# ProPrj_hdmi_3in1out_2024-07-09.net
KiCad netlist of a schematic drawn in EasyEDA Pro
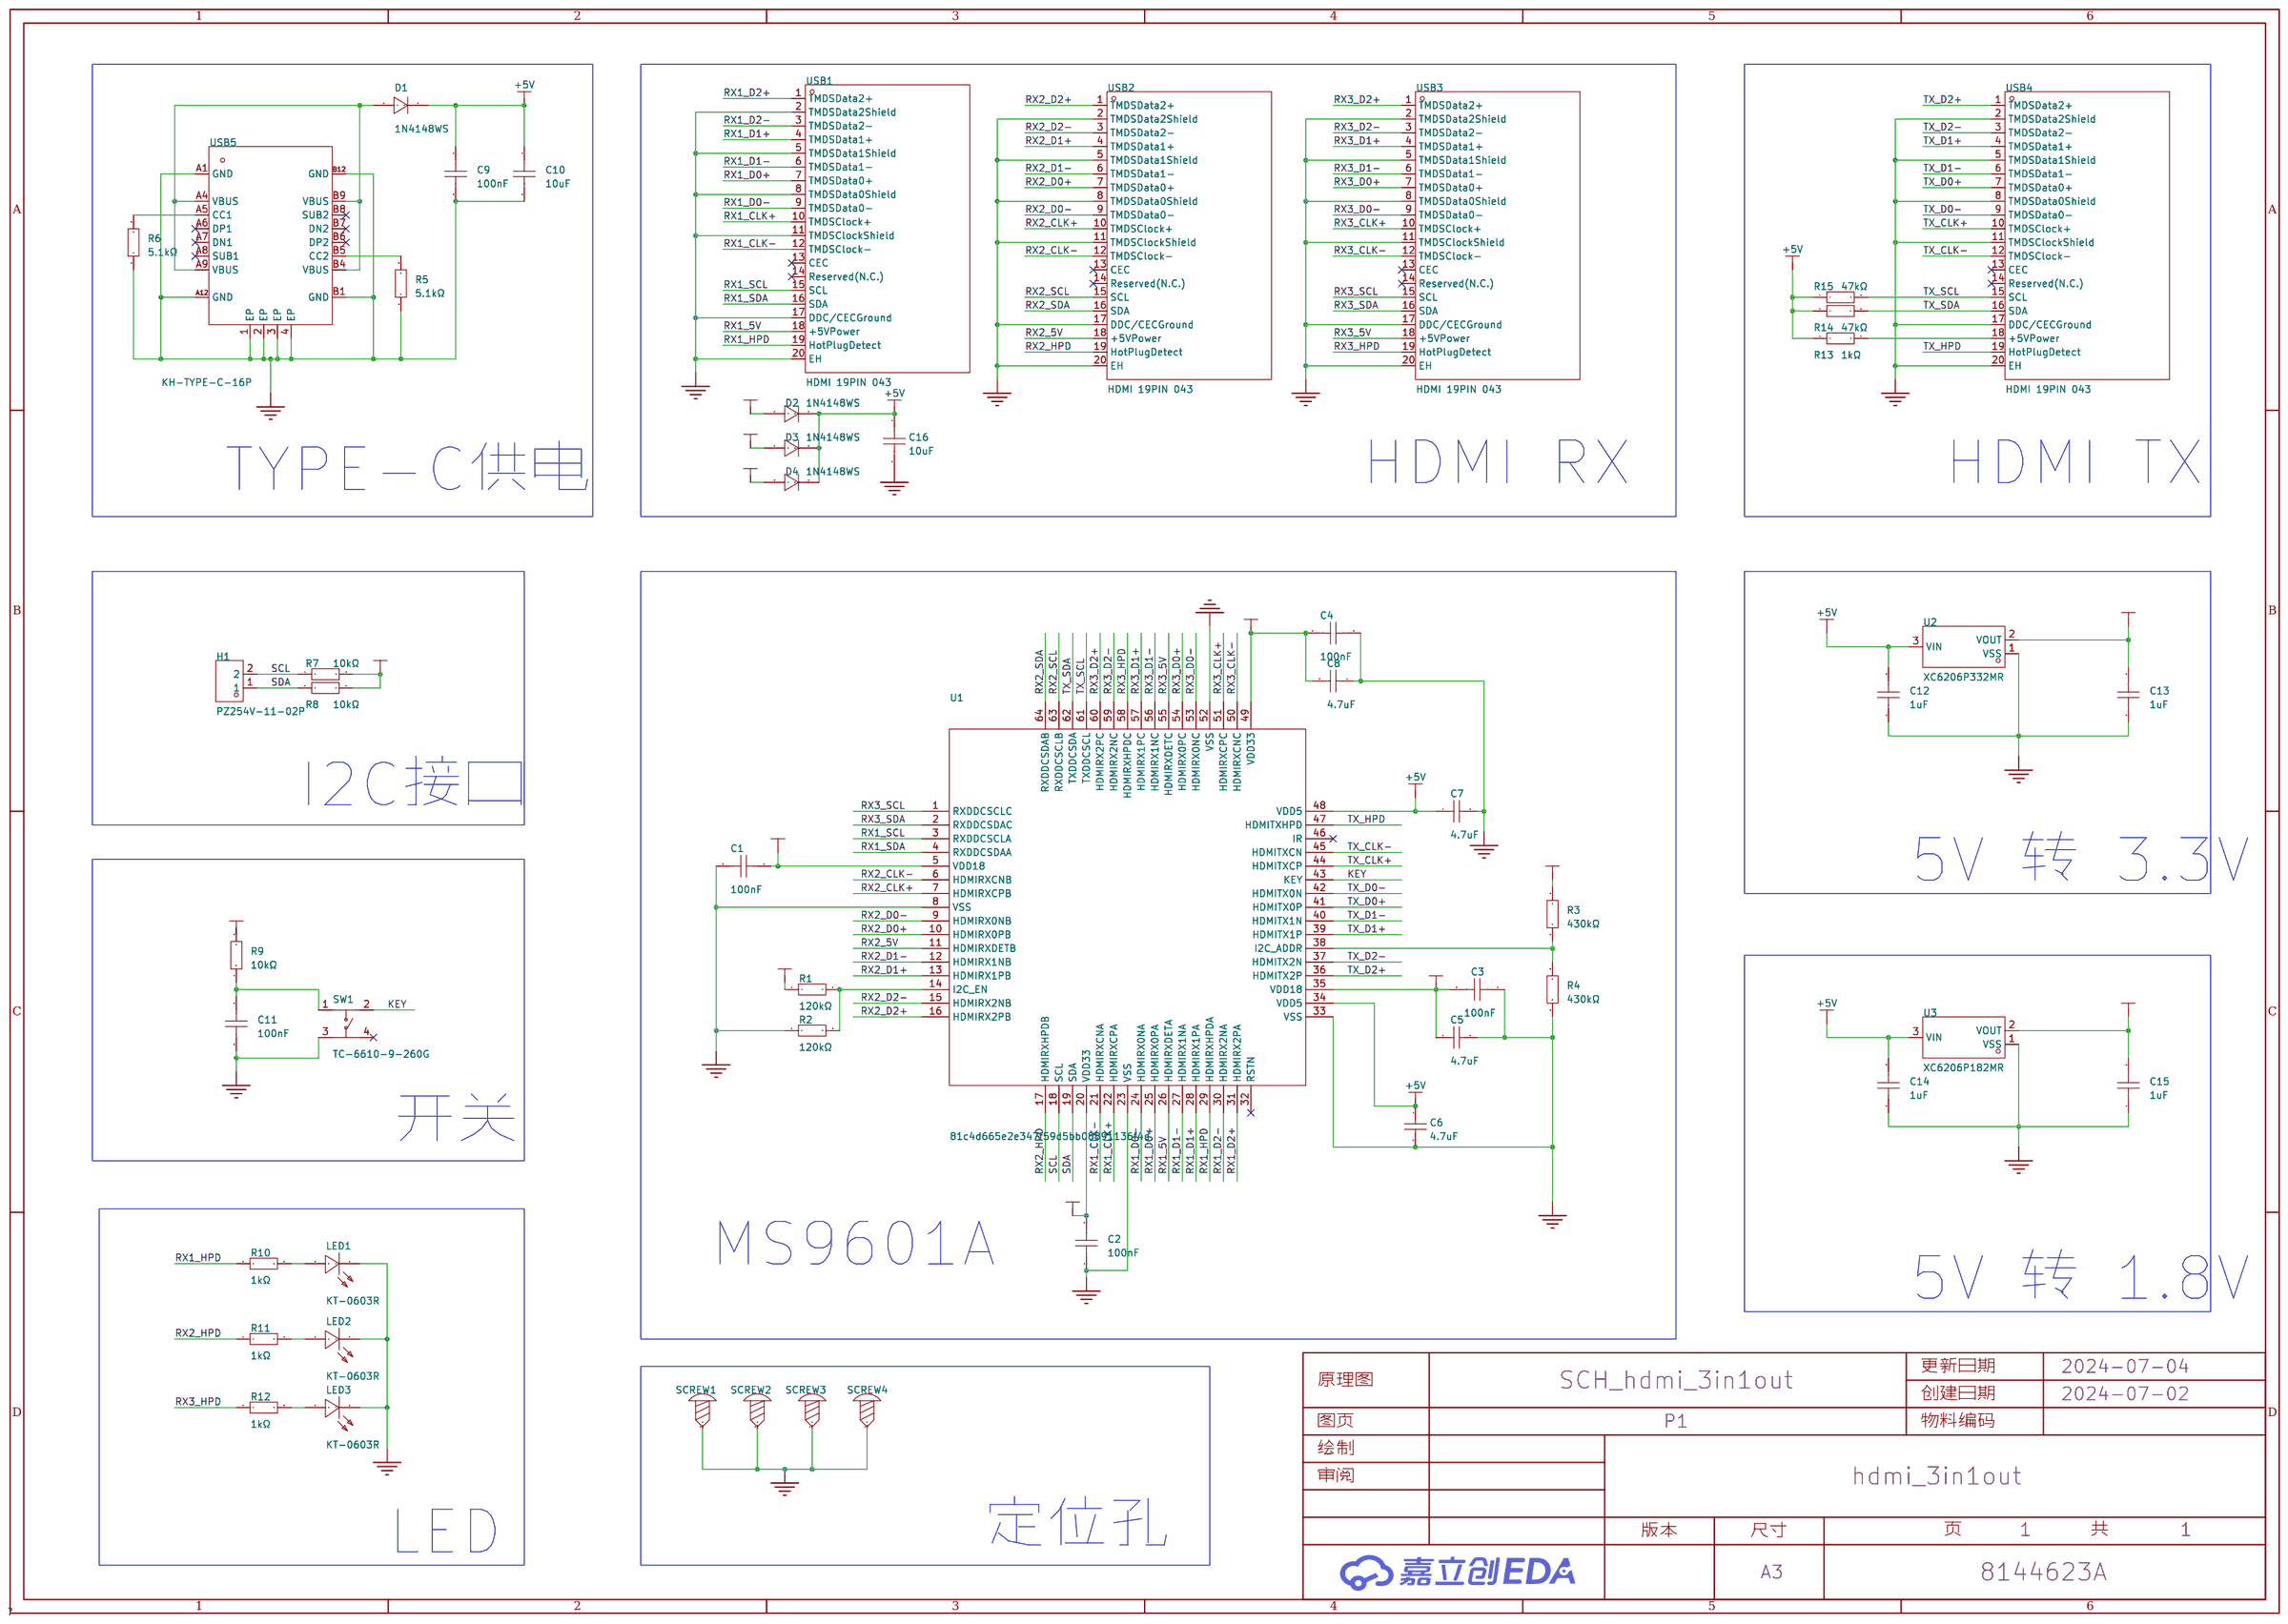
[diagram p0: schematic sheet]

(export (version "E")
  (design (tool "Eeschema 10.0.6"))
  (components
    (comp (ref "C1")
      (value "100nF")
      (footprint "easyedapro:C0603")
      (description "容值:100nF;精度:±10%;额定电压:50V;材质(温度系数):X7R;")
      (fields
        (field (name "Manufacturer Part") "CC0603KRX7R9BB104")
        (field (name "Manufacturer") "YAGEO(国巨)")
      )
      (libsource (lib "easyedapro") (part "CC0603KRX7R9BB104"))
    )
    (comp (ref "C2")
      (value "100nF")
      (footprint "easyedapro:C0603")
      (description "容值:100nF;精度:±10%;额定电压:50V;材质(温度系数):X7R;")
      (fields
        (field (name "Manufacturer Part") "CC0603KRX7R9BB104")
        (field (name "Manufacturer") "YAGEO(国巨)")
      )
      (libsource (lib "easyedapro") (part "CC0603KRX7R9BB104"))
    )
    (comp (ref "C3")
      (value "100nF")
      (footprint "easyedapro:C0603")
      (description "容值:100nF;精度:±10%;额定电压:50V;材质(温度系数):X7R;")
      (fields
        (field (name "Manufacturer Part") "CC0603KRX7R9BB104")
        (field (name "Manufacturer") "YAGEO(国巨)")
      )
      (libsource (lib "easyedapro") (part "CC0603KRX7R9BB104"))
    )
    (comp (ref "C4")
      (value "100nF")
      (footprint "easyedapro:C0603")
      (description "容值:100nF;精度:±10%;额定电压:50V;材质(温度系数):X7R;")
      (fields
        (field (name "Manufacturer Part") "CC0603KRX7R9BB104")
        (field (name "Manufacturer") "YAGEO(国巨)")
      )
      (libsource (lib "easyedapro") (part "CC0603KRX7R9BB104"))
    )
    (comp (ref "C5")
      (value "4.7uF")
      (footprint "easyedapro:C0603")
      (description "容值:4.7uF;精度:±10%;额定电压:16V;材质(温度系数):X5R;")
      (fields
        (field (name "Manufacturer Part") "CL10A475KO8NNNC")
        (field (name "Manufacturer") "SAMSUNG(三星)")
      )
      (libsource (lib "easyedapro") (part "CL10A475KO8NNNC"))
    )
    (comp (ref "C6")
      (value "4.7uF")
      (footprint "easyedapro:C0603")
      (description "容值:4.7uF;精度:±10%;额定电压:16V;材质(温度系数):X5R;")
      (fields
        (field (name "Manufacturer Part") "CL10A475KO8NNNC")
        (field (name "Manufacturer") "SAMSUNG(三星)")
      )
      (libsource (lib "easyedapro") (part "CL10A475KO8NNNC"))
    )
    (comp (ref "C7")
      (value "4.7uF")
      (footprint "easyedapro:C0603")
      (description "容值:4.7uF;精度:±10%;额定电压:16V;材质(温度系数):X5R;")
      (fields
        (field (name "Manufacturer Part") "CL10A475KO8NNNC")
        (field (name "Manufacturer") "SAMSUNG(三星)")
      )
      (libsource (lib "easyedapro") (part "CL10A475KO8NNNC"))
    )
    (comp (ref "C8")
      (value "4.7uF")
      (footprint "easyedapro:C0603")
      (description "容值:4.7uF;精度:±10%;额定电压:16V;材质(温度系数):X5R;")
      (fields
        (field (name "Manufacturer Part") "CL10A475KO8NNNC")
        (field (name "Manufacturer") "SAMSUNG(三星)")
      )
      (libsource (lib "easyedapro") (part "CL10A475KO8NNNC"))
    )
    (comp (ref "C9")
      (value "100nF")
      (footprint "easyedapro:C0603")
      (description "容值:100nF;精度:±10%;额定电压:50V;材质(温度系数):X7R;")
      (fields
        (field (name "Manufacturer Part") "CC0603KRX7R9BB104")
        (field (name "Manufacturer") "YAGEO(国巨)")
      )
      (libsource (lib "easyedapro") (part "CC0603KRX7R9BB104"))
    )
    (comp (ref "C10")
      (value "10uF")
      (footprint "easyedapro:C0603")
      (description "容值:10uF;精度:±10%;额定电压:10V;材质(温度系数):X5R;")
      (fields
        (field (name "Manufacturer Part") "CL10A106KP8NNNC")
        (field (name "Manufacturer") "SAMSUNG(三星)")
      )
      (libsource (lib "easyedapro") (part "CL10A106KP8NNNC"))
    )
    (comp (ref "C11")
      (value "100nF")
      (footprint "easyedapro:C0603")
      (description "容值:100nF;精度:±10%;额定电压:50V;材质(温度系数):X7R;")
      (fields
        (field (name "Manufacturer Part") "CC0603KRX7R9BB104")
        (field (name "Manufacturer") "YAGEO(国巨)")
      )
      (libsource (lib "easyedapro") (part "CC0603KRX7R9BB104"))
    )
    (comp (ref "C12")
      (value "1uF")
      (footprint "easyedapro:C0603")
      (description "容值:1uF;精度:±10%;额定电压:50V;材质(温度系数):X5R;")
      (fields
        (field (name "Manufacturer Part") "CL10A105KB8NNNC")
        (field (name "Manufacturer") "SAMSUNG(三星)")
      )
      (libsource (lib "easyedapro") (part "CL10A105KB8NNNC"))
    )
    (comp (ref "C13")
      (value "1uF")
      (footprint "easyedapro:C0603")
      (description "容值:1uF;精度:±10%;额定电压:50V;材质(温度系数):X5R;")
      (fields
        (field (name "Manufacturer Part") "CL10A105KB8NNNC")
        (field (name "Manufacturer") "SAMSUNG(三星)")
      )
      (libsource (lib "easyedapro") (part "CL10A105KB8NNNC"))
    )
    (comp (ref "C14")
      (value "1uF")
      (footprint "easyedapro:C0603")
      (description "容值:1uF;精度:±10%;额定电压:50V;材质(温度系数):X5R;")
      (fields
        (field (name "Manufacturer Part") "CL10A105KB8NNNC")
        (field (name "Manufacturer") "SAMSUNG(三星)")
      )
      (libsource (lib "easyedapro") (part "CL10A105KB8NNNC"))
    )
    (comp (ref "C15")
      (value "1uF")
      (footprint "easyedapro:C0603")
      (description "容值:1uF;精度:±10%;额定电压:50V;材质(温度系数):X5R;")
      (fields
        (field (name "Manufacturer Part") "CL10A105KB8NNNC")
        (field (name "Manufacturer") "SAMSUNG(三星)")
      )
      (libsource (lib "easyedapro") (part "CL10A105KB8NNNC"))
    )
    (comp (ref "C16")
      (value "10uF")
      (footprint "easyedapro:C0603")
      (description "容值:10uF;精度:±10%;额定电压:10V;材质(温度系数):X5R;")
      (fields
        (field (name "Manufacturer Part") "CL10A106KP8NNNC")
        (field (name "Manufacturer") "SAMSUNG(三星)")
      )
      (libsource (lib "easyedapro") (part "CL10A106KP8NNNC"))
    )
    (comp (ref "D1")
      (value "1N4148WS")
      (footprint "easyedapro:SOD-323_L1.8-W1.3-LS2.5-RD")
      (description "二极管配置:独立式;正向压降(Vf):1.25V@150mA;直流反向耐压(Vr):100V;平均整流电流(Io):150mA;功率:200mW;反向恢复时间(trr):4ns;")
      (fields (field (name "Manufacturer") "CJ(江苏长电/长晶)"))
      (libsource (lib "easyedapro") (part "1N4148WS T4"))
    )
    (comp (ref "D2")
      (value "1N4148WS")
      (footprint "easyedapro:SOD-323_L1.8-W1.3-LS2.5-RD")
      (description "二极管配置:独立式;正向压降(Vf):1.25V@150mA;直流反向耐压(Vr):100V;平均整流电流(Io):150mA;功率:200mW;反向恢复时间(trr):4ns;")
      (fields (field (name "Manufacturer") "CJ(江苏长电/长晶)"))
      (libsource (lib "easyedapro") (part "1N4148WS T4"))
    )
    (comp (ref "D3")
      (value "1N4148WS")
      (footprint "easyedapro:SOD-323_L1.8-W1.3-LS2.5-RD")
      (description "二极管配置:独立式;正向压降(Vf):1.25V@150mA;直流反向耐压(Vr):100V;平均整流电流(Io):150mA;功率:200mW;反向恢复时间(trr):4ns;")
      (fields (field (name "Manufacturer") "CJ(江苏长电/长晶)"))
      (libsource (lib "easyedapro") (part "1N4148WS T4"))
    )
    (comp (ref "D4")
      (value "1N4148WS")
      (footprint "easyedapro:SOD-323_L1.8-W1.3-LS2.5-RD")
      (description "二极管配置:独立式;正向压降(Vf):1.25V@150mA;直流反向耐压(Vr):100V;平均整流电流(Io):150mA;功率:200mW;反向恢复时间(trr):4ns;")
      (fields (field (name "Manufacturer") "CJ(江苏长电/长晶)"))
      (libsource (lib "easyedapro") (part "1N4148WS T4"))
    )
    (comp (ref "H1")
      (value "PZ254V-11-02P")
      (footprint "easyedapro:HDR-TH_2P-P2.54-V-M")
      (fields (field (name "Manufacturer") "XFCN(兴飞)"))
      (libsource (lib "easyedapro") (part "PZ254V-11-02P"))
    )
    (comp (ref "LED1")
      (value "KT-0603R")
      (footprint "easyedapro:LED0603-RD")
      (description "发光颜色:红色;功率:-;正向电流:-;主波长:-;二极管配置:-;透镜颜色:-;色温:-;发光角度:-;载带方式:-;工作温度:-40°C~+85°C;")
      (fields (field (name "Manufacturer") "KENTO"))
      (libsource (lib "easyedapro") (part "KT-0603R"))
    )
    (comp (ref "LED2")
      (value "KT-0603R")
      (footprint "easyedapro:LED0603-RD")
      (description "发光颜色:红色;功率:-;正向电流:-;主波长:-;二极管配置:-;透镜颜色:-;色温:-;发光角度:-;载带方式:-;工作温度:-40°C~+85°C;")
      (fields (field (name "Manufacturer") "KENTO"))
      (libsource (lib "easyedapro") (part "KT-0603R"))
    )
    (comp (ref "LED3")
      (value "KT-0603R")
      (footprint "easyedapro:LED0603-RD")
      (description "发光颜色:红色;功率:-;正向电流:-;主波长:-;二极管配置:-;透镜颜色:-;色温:-;发光角度:-;载带方式:-;工作温度:-40°C~+85°C;")
      (fields (field (name "Manufacturer") "KENTO"))
      (libsource (lib "easyedapro") (part "KT-0603R"))
    )
    (comp (ref "R1")
      (value "120kΩ")
      (footprint "easyedapro:R0603")
      (description "电阻类型:厚膜电阻;阻值:120kΩ;精度:±1%;功率:100mW;最大工作电压:75V;温度系数:±100ppm/°C;")
      (fields
        (field (name "Manufacturer Part") "0603WAF1203T5E")
        (field (name "Manufacturer") "UNI-ROYAL(厚声)")
      )
      (libsource (lib "easyedapro") (part "0603WAF1203T5E"))
    )
    (comp (ref "R2")
      (value "120kΩ")
      (footprint "easyedapro:R0603")
      (description "电阻类型:厚膜电阻;阻值:120kΩ;精度:±1%;功率:100mW;最大工作电压:75V;温度系数:±100ppm/°C;")
      (fields
        (field (name "Manufacturer Part") "0603WAF1203T5E")
        (field (name "Manufacturer") "UNI-ROYAL(厚声)")
      )
      (libsource (lib "easyedapro") (part "0603WAF1203T5E"))
    )
    (comp (ref "R3")
      (value "430kΩ")
      (footprint "easyedapro:R0603")
      (description "电阻类型:厚膜电阻;阻值:430kΩ;精度:±1%;功率:100mW;最大工作电压:75V;温度系数:±100ppm/°C;")
      (fields (field (name "Manufacturer Part") "AC0603FR-07430KL") (field (name "Manufacturer") "YAGEO(国巨)"))
      (libsource (lib "easyedapro") (part "AC0603FR-07430KL"))
    )
    (comp (ref "R4")
      (value "430kΩ")
      (footprint "easyedapro:R0603")
      (description "电阻类型:厚膜电阻;阻值:430kΩ;精度:±1%;功率:100mW;最大工作电压:75V;温度系数:±100ppm/°C;")
      (fields (field (name "Manufacturer Part") "AC0603FR-07430KL") (field (name "Manufacturer") "YAGEO(国巨)"))
      (libsource (lib "easyedapro") (part "AC0603FR-07430KL"))
    )
    (comp (ref "R5")
      (value "5.1kΩ")
      (footprint "easyedapro:R0603")
      (description "电阻类型:厚膜电阻;阻值:5.1kΩ;精度:±1%;功率:100mW;最大工作电压:75V;温度系数:±100ppm/°C;")
      (fields
        (field (name "Manufacturer Part") "0603WAF5101T5E")
        (field (name "Manufacturer") "UNI-ROYAL(厚声)")
      )
      (libsource (lib "easyedapro") (part "0603WAF5101T5E"))
    )
    (comp (ref "R6")
      (value "5.1kΩ")
      (footprint "easyedapro:R0603")
      (description "电阻类型:厚膜电阻;阻值:5.1kΩ;精度:±1%;功率:100mW;最大工作电压:75V;温度系数:±100ppm/°C;")
      (fields
        (field (name "Manufacturer Part") "0603WAF5101T5E")
        (field (name "Manufacturer") "UNI-ROYAL(厚声)")
      )
      (libsource (lib "easyedapro") (part "0603WAF5101T5E"))
    )
    (comp (ref "R7")
      (value "10kΩ")
      (footprint "easyedapro:R0603")
      (description "电阻类型:厚膜电阻;阻值:10kΩ;精度:±1%;功率:100mW;最大工作电压:75V;温度系数:±100ppm/°C;")
      (fields
        (field (name "Manufacturer Part") "0603WAF1002T5E")
        (field (name "Manufacturer") "UNI-ROYAL(厚声)")
      )
      (libsource (lib "easyedapro") (part "0603WAF1002T5E"))
    )
    (comp (ref "R8")
      (value "10kΩ")
      (footprint "easyedapro:R0603")
      (description "电阻类型:厚膜电阻;阻值:10kΩ;精度:±1%;功率:100mW;最大工作电压:75V;温度系数:±100ppm/°C;")
      (fields
        (field (name "Manufacturer Part") "0603WAF1002T5E")
        (field (name "Manufacturer") "UNI-ROYAL(厚声)")
      )
      (libsource (lib "easyedapro") (part "0603WAF1002T5E"))
    )
    (comp (ref "R9")
      (value "10kΩ")
      (footprint "easyedapro:R0603")
      (description "电阻类型:厚膜电阻;阻值:10kΩ;精度:±1%;功率:100mW;最大工作电压:75V;温度系数:±100ppm/°C;")
      (fields
        (field (name "Manufacturer Part") "0603WAF1002T5E")
        (field (name "Manufacturer") "UNI-ROYAL(厚声)")
      )
      (libsource (lib "easyedapro") (part "0603WAF1002T5E"))
    )
    (comp (ref "R10")
      (value "1kΩ")
      (footprint "easyedapro:R0603")
      (description "电阻类型:厚膜电阻;阻值:1kΩ;精度:±1%;功率:100mW;最大工作电压:75V;温度系数:±100ppm/°C;")
      (fields
        (field (name "Manufacturer Part") "0603WAF1001T5E")
        (field (name "Manufacturer") "UNI-ROYAL(厚声)")
      )
      (libsource (lib "easyedapro") (part "0603WAF1001T5E"))
    )
    (comp (ref "R11")
      (value "1kΩ")
      (footprint "easyedapro:R0603")
      (description "电阻类型:厚膜电阻;阻值:1kΩ;精度:±1%;功率:100mW;最大工作电压:75V;温度系数:±100ppm/°C;")
      (fields
        (field (name "Manufacturer Part") "0603WAF1001T5E")
        (field (name "Manufacturer") "UNI-ROYAL(厚声)")
      )
      (libsource (lib "easyedapro") (part "0603WAF1001T5E"))
    )
    (comp (ref "R12")
      (value "1kΩ")
      (footprint "easyedapro:R0603")
      (description "电阻类型:厚膜电阻;阻值:1kΩ;精度:±1%;功率:100mW;最大工作电压:75V;温度系数:±100ppm/°C;")
      (fields
        (field (name "Manufacturer Part") "0603WAF1001T5E")
        (field (name "Manufacturer") "UNI-ROYAL(厚声)")
      )
      (libsource (lib "easyedapro") (part "0603WAF1001T5E"))
    )
    (comp (ref "R13")
      (value "1kΩ")
      (footprint "easyedapro:R0603")
      (description "电阻类型:厚膜电阻;阻值:1kΩ;精度:±1%;功率:100mW;最大工作电压:75V;温度系数:±100ppm/°C;")
      (fields
        (field (name "Manufacturer Part") "0603WAF1001T5E")
        (field (name "Manufacturer") "UNI-ROYAL(厚声)")
      )
      (libsource (lib "easyedapro") (part "0603WAF1001T5E"))
    )
    (comp (ref "R14")
      (value "47kΩ")
      (footprint "easyedapro:R0603")
      (description "电阻类型:厚膜电阻;阻值:47kΩ;精度:±1%;功率:100mW;最大工作电压:75V;温度系数:±100ppm/°C;")
      (fields
        (field (name "Manufacturer Part") "0603WAF4702T5E")
        (field (name "Manufacturer") "UNI-ROYAL(厚声)")
      )
      (libsource (lib "easyedapro") (part "0603WAF4702T5E"))
    )
    (comp (ref "R15")
      (value "47kΩ")
      (footprint "easyedapro:R0603")
      (description "电阻类型:厚膜电阻;阻值:47kΩ;精度:±1%;功率:100mW;最大工作电压:75V;温度系数:±100ppm/°C;")
      (fields
        (field (name "Manufacturer Part") "0603WAF4702T5E")
        (field (name "Manufacturer") "UNI-ROYAL(厚声)")
      )
      (libsource (lib "easyedapro") (part "0603WAF4702T5E"))
    )
    (comp (ref "SCREW1")
      (value "~")
      (footprint "easyedapro:M3螺丝")
      (libsource (lib "easyedapro") (part "螺丝孔"))
    )
    (comp (ref "SCREW2")
      (value "~")
      (footprint "easyedapro:M3螺丝")
      (libsource (lib "easyedapro") (part "螺丝孔"))
    )
    (comp (ref "SCREW3")
      (value "~")
      (footprint "easyedapro:M3螺丝")
      (libsource (lib "easyedapro") (part "螺丝孔"))
    )
    (comp (ref "SCREW4")
      (value "~")
      (footprint "easyedapro:M3螺丝")
      (libsource (lib "easyedapro") (part "螺丝孔"))
    )
    (comp (ref "SW1")
      (value "TC-6610-9-260G")
      (footprint "easyedapro:SW-TH_4P-L5.0-W5.0-P4.50-LS6.5")
      (fields (field (name "Manufacturer") "HCTL(华灿天禄)"))
      (libsource (lib "easyedapro") (part "TC-6610-9-260G"))
    )
    (comp (ref "U1")
      (value "81c4d665e2e347f59d5bb08891136f4d")
      (footprint "easyedapro:LQFP-64_L10.0-W10.0-P0.50-LS12.0-TL")
      (libsource (lib "easyedapro") (part "MS9601A"))
    )
    (comp (ref "U2")
      (value "XC6206P332MR")
      (footprint "easyedapro:SOT-23-3_L3.0-W1.7-P0.95-LS2.9-BR")
      (description "输出类型:固定;最大输入电压:8V;输出电压:3.3V;最大输出电流:250mA;电源纹波抑制比(PSRR):40dB@(1kHz);输出极性:正极;")
      (fields (field (name "Manufacturer") "UMW(友台半导体)"))
      (libsource (lib "easyedapro") (part "XC6206P332MR_C347376"))
    )
    (comp (ref "U3")
      (value "XC6206P182MR")
      (footprint "easyedapro:SOT-23-3_L3.0-W1.7-P0.95-LS2.9-BR")
      (description "输出类型:固定;最大输入电压:8V;输出电压:1.8V;最大输出电流:250mA;电源纹波抑制比(PSRR):40dB@(1kHz);输出极性:正极;")
      (fields (field (name "Manufacturer") "UMW(友台半导体)"))
      (libsource (lib "easyedapro") (part "XC6206P182MR_C347373"))
    )
    (comp (ref "USB1")
      (value "HDMI 19PIN 043")
      (footprint "easyedapro:HDMI-SMD_HDMI-19PIN-043")
      (description "连接器类型:HDMI;公母:母;总PIN位数:19P;安装方式:卧贴;排数:-;额定电流:300mA;工作温度范围:-55°C~+85°C;")
      (fields (field (name "Manufacturer") "SHOU HAN(首韩)"))
      (libsource (lib "easyedapro") (part "HDMI 19PIN 043"))
    )
    (comp (ref "USB2")
      (value "HDMI 19PIN 043")
      (footprint "easyedapro:HDMI-SMD_HDMI-19PIN-043")
      (description "连接器类型:HDMI;公母:母;总PIN位数:19P;安装方式:卧贴;排数:-;额定电流:300mA;工作温度范围:-55°C~+85°C;")
      (fields (field (name "Manufacturer") "SHOU HAN(首韩)"))
      (libsource (lib "easyedapro") (part "HDMI 19PIN 043"))
    )
    (comp (ref "USB3")
      (value "HDMI 19PIN 043")
      (footprint "easyedapro:HDMI-SMD_HDMI-19PIN-043")
      (description "连接器类型:HDMI;公母:母;总PIN位数:19P;安装方式:卧贴;排数:-;额定电流:300mA;工作温度范围:-55°C~+85°C;")
      (fields (field (name "Manufacturer") "SHOU HAN(首韩)"))
      (libsource (lib "easyedapro") (part "HDMI 19PIN 043"))
    )
    (comp (ref "USB4")
      (value "HDMI 19PIN 043")
      (footprint "easyedapro:HDMI-SMD_HDMI-19PIN-043")
      (description "连接器类型:HDMI;公母:母;总PIN位数:19P;安装方式:卧贴;排数:-;额定电流:300mA;工作温度范围:-55°C~+85°C;")
      (fields (field (name "Manufacturer") "SHOU HAN(首韩)"))
      (libsource (lib "easyedapro") (part "HDMI 19PIN 043"))
    )
    (comp (ref "USB5")
      (value "KH-TYPE-C-16P")
      (footprint "easyedapro:USB-C-SMD_KH-TYPE-C-16P")
      (description "连接器类型:Type-C;标准:-;公母:母;端口数量:1;触点数量:16P;安装方式:卧贴;额定电流 - 电源:3A;工作温度范围:-40°C~+85°C;")
      (fields (field (name "Manufacturer") "kinghelm(金航标)"))
      (libsource (lib "easyedapro") (part "KH-TYPE-C-16P"))
    )
  )
  (nets
    (net (code "1") (name "+5V") (class "Default")
      (node (ref "C10") (pin "1") (pinfunction "1_1") (pintype "unspecified"))
      (node (ref "C12") (pin "2") (pinfunction "2_2") (pintype "unspecified"))
      (node (ref "C14") (pin "2") (pinfunction "2_2") (pintype "unspecified"))
      (node (ref "C16") (pin "1") (pinfunction "1_1") (pintype "unspecified"))
      (node (ref "C6") (pin "1") (pinfunction "1_1") (pintype "input"))
      (node (ref "C7") (pin "1") (pinfunction "1_1") (pintype "input"))
      (node (ref "C9") (pin "1") (pinfunction "1_1") (pintype "unspecified"))
      (node (ref "D1") (pin "1") (pinfunction "K_1") (pintype "unspecified"))
      (node (ref "D2") (pin "1") (pinfunction "K_1") (pintype "unspecified"))
      (node (ref "D3") (pin "1") (pinfunction "K_1") (pintype "unspecified"))
      (node (ref "D4") (pin "1") (pinfunction "K_1") (pintype "unspecified"))
      (node (ref "R13") (pin "1") (pinfunction "1_1") (pintype "input"))
      (node (ref "R14") (pin "1") (pinfunction "1_1") (pintype "input"))
      (node (ref "R15") (pin "1") (pinfunction "1_1") (pintype "input"))
      (node (ref "U1") (pin "34") (pinfunction "VDD5_34") (pintype "input"))
      (node (ref "U1") (pin "48") (pinfunction "VDD5_48") (pintype "input"))
      (node (ref "U2") (pin "3") (pinfunction "VIN_3") (pintype "unspecified"))
      (node (ref "U3") (pin "3") (pinfunction "VIN_3") (pintype "unspecified"))
    )
    (net (code "2") (name "/KEY") (class "Default")
      (node (ref "SW1") (pin "2") (pinfunction "2_2") (pintype "input"))
      (node (ref "U1") (pin "43") (pinfunction "KEY_43") (pintype "input"))
    )
    (net (code "3") (name "/RX1_CLK+") (class "Default")
      (node (ref "U1") (pin "22") (pinfunction "HDMIRXCPA_22") (pintype "input"))
      (node (ref "USB1") (pin "10") (pinfunction "TMDSClock+_10") (pintype "unspecified"))
    )
    (net (code "4") (name "/RX1_CLK-") (class "Default")
      (node (ref "U1") (pin "21") (pinfunction "HDMIRXCNA_21") (pintype "input"))
      (node (ref "USB1") (pin "12") (pinfunction "TMDSClock-_12") (pintype "unspecified"))
    )
    (net (code "5") (name "/RX1_D0+") (class "Default")
      (node (ref "U1") (pin "25") (pinfunction "HDMIRX0PA_25") (pintype "input"))
      (node (ref "USB1") (pin "7") (pinfunction "TMDSData0+_7") (pintype "unspecified"))
    )
    (net (code "6") (name "/RX1_D0-") (class "Default")
      (node (ref "U1") (pin "24") (pinfunction "HDMIRX0NA_24") (pintype "input"))
      (node (ref "USB1") (pin "9") (pinfunction "TMDSData0-_9") (pintype "unspecified"))
    )
    (net (code "7") (name "/RX1_D1+") (class "Default")
      (node (ref "U1") (pin "28") (pinfunction "HDMIRX1PA_28") (pintype "input"))
      (node (ref "USB1") (pin "4") (pinfunction "TMDSData1+_4") (pintype "unspecified"))
    )
    (net (code "8") (name "/RX1_D1-") (class "Default")
      (node (ref "U1") (pin "27") (pinfunction "HDMIRX1NA_27") (pintype "input"))
      (node (ref "USB1") (pin "6") (pinfunction "TMDSData1-_6") (pintype "unspecified"))
    )
    (net (code "9") (name "/RX1_D2+") (class "Default")
      (node (ref "U1") (pin "31") (pinfunction "HDMIRX2PA_31") (pintype "input"))
      (node (ref "USB1") (pin "1") (pinfunction "TMDSData2+_1") (pintype "unspecified"))
    )
    (net (code "10") (name "/RX1_D2-") (class "Default")
      (node (ref "U1") (pin "30") (pinfunction "HDMIRX2NA_30") (pintype "input"))
      (node (ref "USB1") (pin "3") (pinfunction "TMDSData2-_3") (pintype "unspecified"))
    )
    (net (code "11") (name "/RX1_HPD") (class "Default")
      (node (ref "R10") (pin "1") (pinfunction "1_1") (pintype "input"))
      (node (ref "U1") (pin "29") (pinfunction "HDMIRXHPDA_29") (pintype "input"))
      (node (ref "USB1") (pin "19") (pinfunction "HotPlugDetect_19") (pintype "unspecified"))
    )
    (net (code "12") (name "/RX1_SCL") (class "Default")
      (node (ref "U1") (pin "3") (pinfunction "RXDDCSCLA_3") (pintype "input"))
      (node (ref "USB1") (pin "15") (pinfunction "SCL_15") (pintype "unspecified"))
    )
    (net (code "13") (name "/RX1_SDA") (class "Default")
      (node (ref "U1") (pin "4") (pinfunction "RXDDCSDAA_4") (pintype "input"))
      (node (ref "USB1") (pin "16") (pinfunction "SDA_16") (pintype "unspecified"))
    )
    (net (code "14") (name "/RX2_CLK+") (class "Default")
      (node (ref "U1") (pin "7") (pinfunction "HDMIRXCPB_7") (pintype "input"))
      (node (ref "USB2") (pin "10") (pinfunction "TMDSClock+_10") (pintype "unspecified"))
    )
    (net (code "15") (name "/RX2_CLK-") (class "Default")
      (node (ref "U1") (pin "6") (pinfunction "HDMIRXCNB_6") (pintype "input"))
      (node (ref "USB2") (pin "12") (pinfunction "TMDSClock-_12") (pintype "unspecified"))
    )
    (net (code "16") (name "/RX2_D0+") (class "Default")
      (node (ref "U1") (pin "10") (pinfunction "HDMIRX0PB_10") (pintype "input"))
      (node (ref "USB2") (pin "7") (pinfunction "TMDSData0+_7") (pintype "unspecified"))
    )
    (net (code "17") (name "/RX2_D0-") (class "Default")
      (node (ref "U1") (pin "9") (pinfunction "HDMIRX0NB_9") (pintype "input"))
      (node (ref "USB2") (pin "9") (pinfunction "TMDSData0-_9") (pintype "unspecified"))
    )
    (net (code "18") (name "/RX2_D1+") (class "Default")
      (node (ref "U1") (pin "13") (pinfunction "HDMIRX1PB_13") (pintype "input"))
      (node (ref "USB2") (pin "4") (pinfunction "TMDSData1+_4") (pintype "unspecified"))
    )
    (net (code "19") (name "/RX2_D1-") (class "Default")
      (node (ref "U1") (pin "12") (pinfunction "HDMIRX1NB_12") (pintype "input"))
      (node (ref "USB2") (pin "6") (pinfunction "TMDSData1-_6") (pintype "unspecified"))
    )
    (net (code "20") (name "/RX2_D2+") (class "Default")
      (node (ref "U1") (pin "16") (pinfunction "HDMIRX2PB_16") (pintype "input"))
      (node (ref "USB2") (pin "1") (pinfunction "TMDSData2+_1") (pintype "unspecified"))
    )
    (net (code "21") (name "/RX2_D2-") (class "Default")
      (node (ref "U1") (pin "15") (pinfunction "HDMIRX2NB_15") (pintype "input"))
      (node (ref "USB2") (pin "3") (pinfunction "TMDSData2-_3") (pintype "unspecified"))
    )
    (net (code "22") (name "/RX2_HPD") (class "Default")
      (node (ref "R11") (pin "1") (pinfunction "1_1") (pintype "input"))
      (node (ref "U1") (pin "17") (pinfunction "HDMIRXHPDB_17") (pintype "input"))
      (node (ref "USB2") (pin "19") (pinfunction "HotPlugDetect_19") (pintype "unspecified"))
    )
    (net (code "23") (name "/RX2_SCL") (class "Default")
      (node (ref "U1") (pin "63") (pinfunction "RXDDCSCLB_63") (pintype "input"))
      (node (ref "USB2") (pin "15") (pinfunction "SCL_15") (pintype "unspecified"))
    )
    (net (code "24") (name "/RX2_SDA") (class "Default")
      (node (ref "U1") (pin "64") (pinfunction "RXDDCSDAB_64") (pintype "input"))
      (node (ref "USB2") (pin "16") (pinfunction "SDA_16") (pintype "unspecified"))
    )
    (net (code "25") (name "/RX3_CLK+") (class "Default")
      (node (ref "U1") (pin "51") (pinfunction "HDMIRXCPC_51") (pintype "input"))
      (node (ref "USB3") (pin "10") (pinfunction "TMDSClock+_10") (pintype "unspecified"))
    )
    (net (code "26") (name "/RX3_CLK-") (class "Default")
      (node (ref "U1") (pin "50") (pinfunction "HDMIRXCNC_50") (pintype "input"))
      (node (ref "USB3") (pin "12") (pinfunction "TMDSClock-_12") (pintype "unspecified"))
    )
    (net (code "27") (name "/RX3_D0+") (class "Default")
      (node (ref "U1") (pin "54") (pinfunction "HDMIRX0PC_54") (pintype "input"))
      (node (ref "USB3") (pin "7") (pinfunction "TMDSData0+_7") (pintype "unspecified"))
    )
    (net (code "28") (name "/RX3_D0-") (class "Default")
      (node (ref "U1") (pin "53") (pinfunction "HDMIRX0NC_53") (pintype "input"))
      (node (ref "USB3") (pin "9") (pinfunction "TMDSData0-_9") (pintype "unspecified"))
    )
    (net (code "29") (name "/RX3_D1+") (class "Default")
      (node (ref "U1") (pin "57") (pinfunction "HDMIRX1PC_57") (pintype "input"))
      (node (ref "USB3") (pin "4") (pinfunction "TMDSData1+_4") (pintype "unspecified"))
    )
    (net (code "30") (name "/RX3_D1-") (class "Default")
      (node (ref "U1") (pin "56") (pinfunction "HDMIRX1NC_56") (pintype "input"))
      (node (ref "USB3") (pin "6") (pinfunction "TMDSData1-_6") (pintype "unspecified"))
    )
    (net (code "31") (name "/RX3_D2+") (class "Default")
      (node (ref "U1") (pin "60") (pinfunction "HDMIRX2PC_60") (pintype "input"))
      (node (ref "USB3") (pin "1") (pinfunction "TMDSData2+_1") (pintype "unspecified"))
    )
    (net (code "32") (name "/RX3_D2-") (class "Default")
      (node (ref "U1") (pin "59") (pinfunction "HDMIRX2NC_59") (pintype "input"))
      (node (ref "USB3") (pin "3") (pinfunction "TMDSData2-_3") (pintype "unspecified"))
    )
    (net (code "33") (name "/RX3_HPD") (class "Default")
      (node (ref "R12") (pin "1") (pinfunction "1_1") (pintype "input"))
      (node (ref "U1") (pin "58") (pinfunction "HDMIRXHPDC_58") (pintype "input"))
      (node (ref "USB3") (pin "19") (pinfunction "HotPlugDetect_19") (pintype "unspecified"))
    )
    (net (code "34") (name "/RX3_SCL") (class "Default")
      (node (ref "U1") (pin "1") (pinfunction "RXDDCSCLC_1") (pintype "input"))
      (node (ref "USB3") (pin "15") (pinfunction "SCL_15") (pintype "unspecified"))
    )
    (net (code "35") (name "/RX3_SDA") (class "Default")
      (node (ref "U1") (pin "2") (pinfunction "RXDDCSDAC_2") (pintype "input"))
      (node (ref "USB3") (pin "16") (pinfunction "SDA_16") (pintype "unspecified"))
    )
    (net (code "36") (name "/SCL") (class "Default")
      (node (ref "H1") (pin "2") (pinfunction "2_2") (pintype "unspecified"))
      (node (ref "R7") (pin "1") (pinfunction "1_1") (pintype "input"))
      (node (ref "U1") (pin "18") (pinfunction "SCL_18") (pintype "input"))
    )
    (net (code "37") (name "/SDA") (class "Default")
      (node (ref "H1") (pin "1") (pinfunction "1_1") (pintype "unspecified"))
      (node (ref "R8") (pin "1") (pinfunction "1_1") (pintype "input"))
      (node (ref "U1") (pin "19") (pinfunction "SDA_19") (pintype "input"))
    )
    (net (code "38") (name "/TX_CLK+") (class "Default")
      (node (ref "U1") (pin "44") (pinfunction "HDMITXCP_44") (pintype "input"))
      (node (ref "USB4") (pin "10") (pinfunction "TMDSClock+_10") (pintype "unspecified"))
    )
    (net (code "39") (name "/TX_CLK-") (class "Default")
      (node (ref "U1") (pin "45") (pinfunction "HDMITXCN_45") (pintype "input"))
      (node (ref "USB4") (pin "12") (pinfunction "TMDSClock-_12") (pintype "unspecified"))
    )
    (net (code "40") (name "/TX_D0+") (class "Default")
      (node (ref "U1") (pin "41") (pinfunction "HDMITX0P_41") (pintype "input"))
      (node (ref "USB4") (pin "7") (pinfunction "TMDSData0+_7") (pintype "unspecified"))
    )
    (net (code "41") (name "/TX_D0-") (class "Default")
      (node (ref "U1") (pin "42") (pinfunction "HDMITX0N_42") (pintype "input"))
      (node (ref "USB4") (pin "9") (pinfunction "TMDSData0-_9") (pintype "unspecified"))
    )
    (net (code "42") (name "/TX_D1+") (class "Default")
      (node (ref "U1") (pin "39") (pinfunction "HDMITX1P_39") (pintype "input"))
      (node (ref "USB4") (pin "4") (pinfunction "TMDSData1+_4") (pintype "unspecified"))
    )
    (net (code "43") (name "/TX_D1-") (class "Default")
      (node (ref "U1") (pin "40") (pinfunction "HDMITX1N_40") (pintype "input"))
      (node (ref "USB4") (pin "6") (pinfunction "TMDSData1-_6") (pintype "unspecified"))
    )
    (net (code "44") (name "/TX_D2+") (class "Default")
      (node (ref "U1") (pin "36") (pinfunction "HDMITX2P_36") (pintype "input"))
      (node (ref "USB4") (pin "1") (pinfunction "TMDSData2+_1") (pintype "unspecified"))
    )
    (net (code "45") (name "/TX_D2-") (class "Default")
      (node (ref "U1") (pin "37") (pinfunction "HDMITX2N_37") (pintype "input"))
      (node (ref "USB4") (pin "3") (pinfunction "TMDSData2-_3") (pintype "unspecified"))
    )
    (net (code "46") (name "/TX_HPD") (class "Default")
      (node (ref "U1") (pin "47") (pinfunction "HDMITXHPD_47") (pintype "input"))
      (node (ref "USB4") (pin "19") (pinfunction "HotPlugDetect_19") (pintype "unspecified"))
    )
    (net (code "47") (name "/TX_SCL") (class "Default")
      (node (ref "R15") (pin "2") (pinfunction "2_2") (pintype "input"))
      (node (ref "U1") (pin "61") (pinfunction "TXDDCSCL_61") (pintype "input"))
      (node (ref "USB4") (pin "15") (pinfunction "SCL_15") (pintype "unspecified"))
    )
    (net (code "48") (name "/TX_SDA") (class "Default")
      (node (ref "R14") (pin "2") (pinfunction "2_2") (pintype "input"))
      (node (ref "U1") (pin "62") (pinfunction "TXDDCSDA_62") (pintype "input"))
      (node (ref "USB4") (pin "16") (pinfunction "SDA_16") (pintype "unspecified"))
    )
    (net (code "49") (name "1.8V") (class "Default")
      (node (ref "C1") (pin "1") (pinfunction "1_1") (pintype "unspecified"))
      (node (ref "C15") (pin "2") (pinfunction "2_2") (pintype "unspecified"))
      (node (ref "C3") (pin "2") (pinfunction "2_2") (pintype "unspecified"))
      (node (ref "C5") (pin "1") (pinfunction "1_1") (pintype "input"))
      (node (ref "U1") (pin "35") (pinfunction "VDD18_35") (pintype "input"))
      (node (ref "U1") (pin "5") (pinfunction "VDD18_5") (pintype "input"))
      (node (ref "U3") (pin "2") (pinfunction "VOUT_2") (pintype "unspecified"))
    )
    (net (code "50") (name "3.3V") (class "Default")
      (node (ref "C13") (pin "2") (pinfunction "2_2") (pintype "unspecified"))
      (node (ref "C2") (pin "2") (pinfunction "2_2") (pintype "unspecified"))
      (node (ref "C4") (pin "1") (pinfunction "1_1") (pintype "unspecified"))
      (node (ref "C8") (pin "2") (pinfunction "2_2") (pintype "input"))
      (node (ref "R1") (pin "1") (pinfunction "1_1") (pintype "input"))
      (node (ref "R3") (pin "2") (pinfunction "2_2") (pintype "unspecified"))
      (node (ref "R7") (pin "2") (pinfunction "2_2") (pintype "input"))
      (node (ref "R8") (pin "2") (pinfunction "2_2") (pintype "input"))
      (node (ref "R9") (pin "2") (pinfunction "2_2") (pintype "input"))
      (node (ref "U1") (pin "20") (pinfunction "VDD33_20") (pintype "input"))
      (node (ref "U1") (pin "49") (pinfunction "VDD33_49") (pintype "input"))
      (node (ref "U2") (pin "2") (pinfunction "VOUT_2") (pintype "unspecified"))
    )
    (net (code "51") (name "GND") (class "Default")
      (node (ref "C1") (pin "2") (pinfunction "2_2") (pintype "unspecified"))
      (node (ref "C10") (pin "2") (pinfunction "2_2") (pintype "unspecified"))
      (node (ref "C11") (pin "2") (pinfunction "2_2") (pintype "unspecified"))
      (node (ref "C12") (pin "1") (pinfunction "1_1") (pintype "unspecified"))
      (node (ref "C13") (pin "1") (pinfunction "1_1") (pintype "unspecified"))
      (node (ref "C14") (pin "1") (pinfunction "1_1") (pintype "unspecified"))
      (node (ref "C15") (pin "1") (pinfunction "1_1") (pintype "unspecified"))
      (node (ref "C16") (pin "2") (pinfunction "2_2") (pintype "unspecified"))
      (node (ref "C2") (pin "1") (pinfunction "1_1") (pintype "unspecified"))
      (node (ref "C3") (pin "1") (pinfunction "1_1") (pintype "unspecified"))
      (node (ref "C4") (pin "2") (pinfunction "2_2") (pintype "unspecified"))
      (node (ref "C5") (pin "2") (pinfunction "2_2") (pintype "input"))
      (node (ref "C6") (pin "2") (pinfunction "2_2") (pintype "input"))
      (node (ref "C7") (pin "2") (pinfunction "2_2") (pintype "input"))
      (node (ref "C8") (pin "1") (pinfunction "1_1") (pintype "input"))
      (node (ref "C9") (pin "2") (pinfunction "2_2") (pintype "unspecified"))
      (node (ref "LED1") (pin "1") (pinfunction "K_1") (pintype "input"))
      (node (ref "LED2") (pin "1") (pinfunction "K_1") (pintype "input"))
      (node (ref "LED3") (pin "1") (pinfunction "K_1") (pintype "input"))
      (node (ref "R2") (pin "1") (pinfunction "1_1") (pintype "input"))
      (node (ref "R4") (pin "1") (pinfunction "1_1") (pintype "unspecified"))
      (node (ref "R5") (pin "1") (pinfunction "1_1") (pintype "input"))
      (node (ref "R6") (pin "1") (pinfunction "1_1") (pintype "input"))
      (node (ref "SCREW1") (pin "1") (pinfunction "1_1") (pintype "input"))
      (node (ref "SCREW2") (pin "1") (pinfunction "1_1") (pintype "input"))
      (node (ref "SCREW3") (pin "1") (pinfunction "1_1") (pintype "input"))
      (node (ref "SCREW4") (pin "1") (pinfunction "1_1") (pintype "input"))
      (node (ref "SW1") (pin "3") (pinfunction "3_3") (pintype "input"))
      (node (ref "U1") (pin "23") (pinfunction "VSS_23") (pintype "input"))
      (node (ref "U1") (pin "33") (pinfunction "VSS_33") (pintype "input"))
      (node (ref "U1") (pin "52") (pinfunction "VSS_52") (pintype "input"))
      (node (ref "U1") (pin "8") (pinfunction "VSS_8") (pintype "input"))
      (node (ref "U2") (pin "1") (pinfunction "VSS_1") (pintype "unspecified"))
      (node (ref "U3") (pin "1") (pinfunction "VSS_1") (pintype "unspecified"))
      (node (ref "USB1") (pin "11") (pinfunction "TMDSClockShield_11") (pintype "unspecified"))
      (node (ref "USB1") (pin "17") (pinfunction "DDC/CECGround_17") (pintype "unspecified"))
      (node (ref "USB1") (pin "2") (pinfunction "TMDSData2Shield_2") (pintype "unspecified"))
      (node (ref "USB1") (pin "20") (pinfunction "EH_20") (pintype "unspecified"))
      (node (ref "USB1") (pin "5") (pinfunction "TMDSData1Shield_5") (pintype "unspecified"))
      (node (ref "USB1") (pin "8") (pinfunction "TMDSData0Shield_8") (pintype "unspecified"))
      (node (ref "USB2") (pin "11") (pinfunction "TMDSClockShield_11") (pintype "unspecified"))
      (node (ref "USB2") (pin "17") (pinfunction "DDC/CECGround_17") (pintype "unspecified"))
      (node (ref "USB2") (pin "2") (pinfunction "TMDSData2Shield_2") (pintype "unspecified"))
      (node (ref "USB2") (pin "20") (pinfunction "EH_20") (pintype "unspecified"))
      (node (ref "USB2") (pin "5") (pinfunction "TMDSData1Shield_5") (pintype "unspecified"))
      (node (ref "USB2") (pin "8") (pinfunction "TMDSData0Shield_8") (pintype "unspecified"))
      (node (ref "USB3") (pin "11") (pinfunction "TMDSClockShield_11") (pintype "unspecified"))
      (node (ref "USB3") (pin "17") (pinfunction "DDC/CECGround_17") (pintype "unspecified"))
      (node (ref "USB3") (pin "2") (pinfunction "TMDSData2Shield_2") (pintype "unspecified"))
      (node (ref "USB3") (pin "20") (pinfunction "EH_20") (pintype "unspecified"))
      (node (ref "USB3") (pin "5") (pinfunction "TMDSData1Shield_5") (pintype "unspecified"))
      (node (ref "USB3") (pin "8") (pinfunction "TMDSData0Shield_8") (pintype "unspecified"))
      (node (ref "USB4") (pin "11") (pinfunction "TMDSClockShield_11") (pintype "unspecified"))
      (node (ref "USB4") (pin "17") (pinfunction "DDC/CECGround_17") (pintype "unspecified"))
      (node (ref "USB4") (pin "2") (pinfunction "TMDSData2Shield_2") (pintype "unspecified"))
      (node (ref "USB4") (pin "20") (pinfunction "EH_20") (pintype "unspecified"))
      (node (ref "USB4") (pin "5") (pinfunction "TMDSData1Shield_5") (pintype "unspecified"))
      (node (ref "USB4") (pin "8") (pinfunction "TMDSData0Shield_8") (pintype "unspecified"))
      (node (ref "USB5") (pin "1") (pinfunction "EP_1") (pintype "unspecified"))
      (node (ref "USB5") (pin "2") (pinfunction "EP_2") (pintype "unspecified"))
      (node (ref "USB5") (pin "3") (pinfunction "EP_3") (pintype "unspecified"))
      (node (ref "USB5") (pin "4") (pinfunction "EP_4") (pintype "unspecified"))
      (node (ref "USB5") (pin "A1") (pinfunction "GND_A1") (pintype "unspecified"))
      (node (ref "USB5") (pin "A12") (pinfunction "GND_A12") (pintype "unspecified"))
      (node (ref "USB5") (pin "B1") (pinfunction "GND_B1") (pintype "unspecified"))
      (node (ref "USB5") (pin "B12") (pinfunction "GND_B12") (pintype "unspecified"))
    )
    (net (code "52") (name "Net-(C11-Pad1)") (class "Default")
      (node (ref "C11") (pin "1") (pinfunction "1_1") (pintype "unspecified"))
      (node (ref "R9") (pin "1") (pinfunction "1_1") (pintype "input"))
      (node (ref "SW1") (pin "1") (pinfunction "1_1") (pintype "input"))
    )
    (net (code "53") (name "Net-(D1-A)") (class "Default")
      (node (ref "D1") (pin "2") (pinfunction "A_2") (pintype "unspecified"))
      (node (ref "USB5") (pin "A4") (pinfunction "VBUS_A4") (pintype "unspecified"))
      (node (ref "USB5") (pin "A9") (pinfunction "VBUS_A9") (pintype "unspecified"))
      (node (ref "USB5") (pin "B4") (pinfunction "VBUS_B4") (pintype "unspecified"))
      (node (ref "USB5") (pin "B9") (pinfunction "VBUS_B9") (pintype "unspecified"))
    )
    (net (code "54") (name "Net-(LED1-A)") (class "Default")
      (node (ref "LED1") (pin "2") (pinfunction "A_2") (pintype "input"))
      (node (ref "R10") (pin "2") (pinfunction "2_2") (pintype "input"))
    )
    (net (code "55") (name "Net-(LED2-A)") (class "Default")
      (node (ref "LED2") (pin "2") (pinfunction "A_2") (pintype "input"))
      (node (ref "R11") (pin "2") (pinfunction "2_2") (pintype "input"))
    )
    (net (code "56") (name "Net-(LED3-A)") (class "Default")
      (node (ref "LED3") (pin "2") (pinfunction "A_2") (pintype "input"))
      (node (ref "R12") (pin "2") (pinfunction "2_2") (pintype "input"))
    )
    (net (code "57") (name "Net-(U1-I2C_ADDR)") (class "Default")
      (node (ref "R3") (pin "1") (pinfunction "1_1") (pintype "unspecified"))
      (node (ref "R4") (pin "2") (pinfunction "2_2") (pintype "unspecified"))
      (node (ref "U1") (pin "38") (pinfunction "I2C_ADDR_38") (pintype "input"))
    )
    (net (code "58") (name "Net-(U1-I2C_EN)") (class "Default")
      (node (ref "R1") (pin "2") (pinfunction "2_2") (pintype "input"))
      (node (ref "R2") (pin "2") (pinfunction "2_2") (pintype "input"))
      (node (ref "U1") (pin "14") (pinfunction "I2C_EN_14") (pintype "input"))
    )
    (net (code "59") (name "Net-(USB4-+5VPower)") (class "Default")
      (node (ref "R13") (pin "2") (pinfunction "2_2") (pintype "input"))
      (node (ref "USB4") (pin "18") (pinfunction "+5VPower_18") (pintype "unspecified"))
    )
    (net (code "60") (name "Net-(USB5-CC1)") (class "Default")
      (node (ref "R6") (pin "2") (pinfunction "2_2") (pintype "input"))
      (node (ref "USB5") (pin "A5") (pinfunction "CC1_A5") (pintype "unspecified"))
    )
    (net (code "61") (name "Net-(USB5-CC2)") (class "Default")
      (node (ref "R5") (pin "2") (pinfunction "2_2") (pintype "input"))
      (node (ref "USB5") (pin "B5") (pinfunction "CC2_B5") (pintype "unspecified"))
    )
    (net (code "62") (name "RX1_5V") (class "Default")
      (node (ref "D2") (pin "2") (pinfunction "A_2") (pintype "unspecified"))
      (node (ref "U1") (pin "26") (pinfunction "HDMIRXDETA_26") (pintype "input"))
      (node (ref "USB1") (pin "18") (pinfunction "+5VPower_18") (pintype "unspecified"))
    )
    (net (code "63") (name "RX2_5V") (class "Default")
      (node (ref "D3") (pin "2") (pinfunction "A_2") (pintype "unspecified"))
      (node (ref "U1") (pin "11") (pinfunction "HDMIRXDETB_11") (pintype "input"))
      (node (ref "USB2") (pin "18") (pinfunction "+5VPower_18") (pintype "unspecified"))
    )
    (net (code "64") (name "RX3_5V") (class "Default")
      (node (ref "D4") (pin "2") (pinfunction "A_2") (pintype "unspecified"))
      (node (ref "U1") (pin "55") (pinfunction "HDMIRXDETC_55") (pintype "input"))
      (node (ref "USB3") (pin "18") (pinfunction "+5VPower_18") (pintype "unspecified"))
    )
    (net (code "65") (name "unconnected-(SW1-Pad4)") (class "Default")
      (node (ref "SW1") (pin "4") (pinfunction "4_4") (pintype "input+no_connect"))
    )
    (net (code "66") (name "unconnected-(U1-IR-Pad46)") (class "Default")
      (node (ref "U1") (pin "46") (pinfunction "IR_46") (pintype "input+no_connect"))
    )
    (net (code "67") (name "unconnected-(U1-RSTN-Pad32)") (class "Default")
      (node (ref "U1") (pin "32") (pinfunction "RSTN_32") (pintype "input+no_connect"))
    )
    (net (code "68") (name "unconnected-(USB1-CEC-Pad13)") (class "Default")
      (node (ref "USB1") (pin "13") (pinfunction "CEC_13") (pintype "unspecified+no_connect"))
    )
    (net (code "69") (name "unconnected-(USB1-Reserved(N.C.)-Pad14)") (class "Default")
      (node (ref "USB1") (pin "14") (pinfunction "Reserved(N.C.)_14") (pintype "unspecified+no_connect"))
    )
    (net (code "70") (name "unconnected-(USB2-CEC-Pad13)") (class "Default")
      (node (ref "USB2") (pin "13") (pinfunction "CEC_13") (pintype "unspecified+no_connect"))
    )
    (net (code "71") (name "unconnected-(USB2-Reserved(N.C.)-Pad14)") (class "Default")
      (node (ref "USB2") (pin "14") (pinfunction "Reserved(N.C.)_14") (pintype "unspecified+no_connect"))
    )
    (net (code "72") (name "unconnected-(USB3-CEC-Pad13)") (class "Default")
      (node (ref "USB3") (pin "13") (pinfunction "CEC_13") (pintype "unspecified+no_connect"))
    )
    (net (code "73") (name "unconnected-(USB3-Reserved(N.C.)-Pad14)") (class "Default")
      (node (ref "USB3") (pin "14") (pinfunction "Reserved(N.C.)_14") (pintype "unspecified+no_connect"))
    )
    (net (code "74") (name "unconnected-(USB4-CEC-Pad13)") (class "Default")
      (node (ref "USB4") (pin "13") (pinfunction "CEC_13") (pintype "unspecified+no_connect"))
    )
    (net (code "75") (name "unconnected-(USB4-Reserved(N.C.)-Pad14)") (class "Default")
      (node (ref "USB4") (pin "14") (pinfunction "Reserved(N.C.)_14") (pintype "unspecified+no_connect"))
    )
    (net (code "76") (name "unconnected-(USB5-DN1-PadA7)") (class "Default")
      (node (ref "USB5") (pin "A7") (pinfunction "DN1_A7") (pintype "unspecified+no_connect"))
    )
    (net (code "77") (name "unconnected-(USB5-DN2-PadB7)") (class "Default")
      (node (ref "USB5") (pin "B7") (pinfunction "DN2_B7") (pintype "unspecified+no_connect"))
    )
    (net (code "78") (name "unconnected-(USB5-DP1-PadA6)") (class "Default")
      (node (ref "USB5") (pin "A6") (pinfunction "DP1_A6") (pintype "unspecified+no_connect"))
    )
    (net (code "79") (name "unconnected-(USB5-DP2-PadB6)") (class "Default")
      (node (ref "USB5") (pin "B6") (pinfunction "DP2_B6") (pintype "unspecified+no_connect"))
    )
    (net (code "80") (name "unconnected-(USB5-SUB1-PadA8)") (class "Default")
      (node (ref "USB5") (pin "A8") (pinfunction "SUB1_A8") (pintype "unspecified+no_connect"))
    )
    (net (code "81") (name "unconnected-(USB5-SUB2-PadB8)") (class "Default")
      (node (ref "USB5") (pin "B8") (pinfunction "SUB2_B8") (pintype "unspecified+no_connect"))
    )
  )
)
